# 02-CPU.net
KiCad netlist of a schematic drawn in Altium Designer
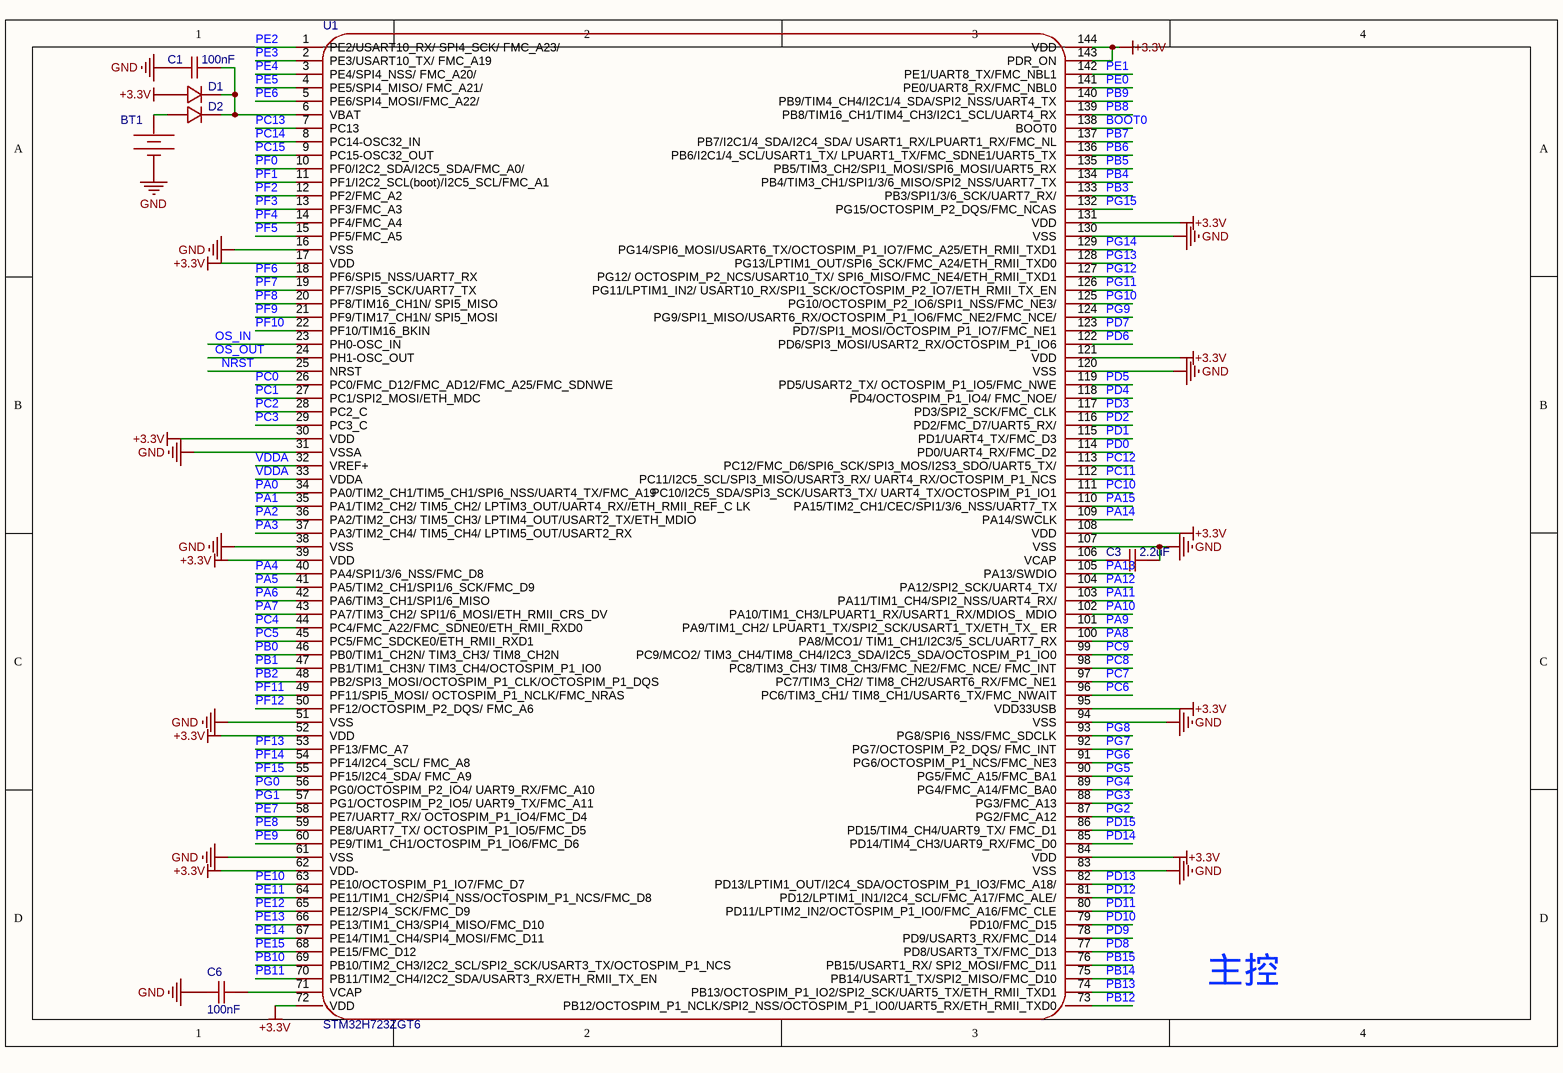
[diagram p0: 02-CPU.SchDoc]

(export (version "E")
  (design (tool "Eeschema 10.0.6"))
  (components
    (comp (ref "BT1")
      (value "BS-12-B3AA003")
      (footprint "BAT-SMD_BS-12-B3AA011")
      (description "连接器类型:电池底座;适用电池规格:CR1220;工作温度范围:-25℃~+85℃;")
      (fields (field (name "MANUFACTURER") "MYOUNG(美阳)"))
      (libsource (lib "altium-import") (part "root_3_BS-12-B3AA003_"))
    )
    (comp (ref "C1")
      (value "100nF")
      (footprint "C0603")
      (fields (field (name "Comment") "CAP_0603"))
      (libsource (lib "altium-import") (part "root_2_CAP_0603_"))
    )
    (comp (ref "C3")
      (value "2.2uF")
      (footprint "C0603")
      (fields (field (name "Comment") "CAP_0603"))
      (libsource (lib "altium-import") (part "root_2_CAP_0603_"))
    )
    (comp (ref "C6")
      (value "100nF")
      (footprint "C0603")
      (fields (field (name "Comment") "CAP_0603"))
      (libsource (lib "altium-import") (part "root_0_CAP_0603_"))
    )
    (comp (ref "D1")
      (value "LL4148_C9808")
      (footprint "LL-34_L3.5-W1.5-RD")
      (fields (field (name "MANUFACTURER") "ST(先科)") (field (name "MANUFACTURERPART") "LL4148"))
      (libsource (lib "altium-import") (part "root_2_LL4148_C9808_"))
    )
    (comp (ref "D2")
      (value "LL4148_C9808")
      (footprint "LL-34_L3.5-W1.5-RD")
      (fields (field (name "MANUFACTURER") "ST(先科)") (field (name "MANUFACTURERPART") "LL4148"))
      (libsource (lib "altium-import") (part "root_2_LL4148_C9808_"))
    )
    (comp (ref "U1")
      (value "STM32H723ZGT6")
      (footprint "LQFP-144_20.0X20.0X0.5P")
      (description "ARM-M系列 CPU最大主频：550MHz 程序存储容量：1MB 程序存储器类型：FLASH RAM总容量：564KB GPIO端口数量：80")
      (libsource (lib "altium-import") (part "root_0_STM32H723ZGT6_"))
    )
  )
  (nets
    (net (code "1") (name "+3.3V") (class "Default")
      (node (ref "D1") (pin "2") (pinfunction "A_2") (pintype "passive"))
      (node (ref "U1") (pin "108") (pinfunction "VDD_108") (pintype "passive"))
      (node (ref "U1") (pin "121") (pinfunction "VDD_121") (pintype "passive"))
      (node (ref "U1") (pin "131") (pinfunction "VDD_131") (pintype "passive"))
      (node (ref "U1") (pin "143") (pinfunction "PDR_ON_143") (pintype "passive"))
      (node (ref "U1") (pin "144") (pinfunction "VDD_144") (pintype "passive"))
      (node (ref "U1") (pin "17") (pinfunction "VDD_17") (pintype "passive"))
      (node (ref "U1") (pin "30") (pinfunction "VDD_30") (pintype "passive"))
      (node (ref "U1") (pin "39") (pinfunction "VDD_39") (pintype "passive"))
      (node (ref "U1") (pin "52") (pinfunction "VDD_52") (pintype "passive"))
      (node (ref "U1") (pin "62") (pinfunction "VDD-_62") (pintype "passive"))
      (node (ref "U1") (pin "72") (pinfunction "VDD_72") (pintype "passive"))
      (node (ref "U1") (pin "84") (pinfunction "VDD_84") (pintype "passive"))
      (node (ref "U1") (pin "95") (pinfunction "VDD33USB_95") (pintype "passive"))
    )
    (net (code "2") (name "/BOOT0") (class "Default")
      (node (ref "U1") (pin "138") (pinfunction "BOOT0_138") (pintype "passive"))
    )
    (net (code "3") (name "/NRST") (class "Default")
      (node (ref "U1") (pin "25") (pinfunction "NRST_25") (pintype "passive"))
    )
    (net (code "4") (name "/OS_IN") (class "Default")
      (node (ref "U1") (pin "23") (pinfunction "PH0-OSC_IN_23") (pintype "passive"))
    )
    (net (code "5") (name "/OS_OUT") (class "Default")
      (node (ref "U1") (pin "24") (pinfunction "PH1-OSC_OUT_24") (pintype "passive"))
    )
    (net (code "6") (name "/PA0") (class "Default")
      (node (ref "U1") (pin "34") (pinfunction "PA0/TIM2_CH1/TIM5_CH1/SPI6_NSS/UART4_TX/FMC_A19_34") (pintype "passive"))
    )
    (net (code "7") (name "/PA1") (class "Default")
      (node (ref "U1") (pin "35") (pinfunction "PA1/TIM2_CH2/_TIM5_CH2/_LPTIM3_OUT/UART4_RX//ETH_RMII_REF_C_LK_35") (pintype "passive"))
    )
    (net (code "8") (name "/PA2") (class "Default")
      (node (ref "U1") (pin "36") (pinfunction "PA2/TIM2_CH3/_TIM5_CH3/_LPTIM4_OUT/USART2_TX/ETH_MDIO_36") (pintype "passive"))
    )
    (net (code "9") (name "/PA3") (class "Default")
      (node (ref "U1") (pin "37") (pinfunction "PA3/TIM2_CH4/_TIM5_CH4/_LPTIM5_OUT/USART2_RX_37") (pintype "passive"))
    )
    (net (code "10") (name "/PA4") (class "Default")
      (node (ref "U1") (pin "40") (pinfunction "PA4/SPI1/3/6_NSS/FMC_D8_40") (pintype "passive"))
    )
    (net (code "11") (name "/PA5") (class "Default")
      (node (ref "U1") (pin "41") (pinfunction "PA5/TIM2_CH1/SPI1/6_SCK/FMC_D9_41") (pintype "passive"))
    )
    (net (code "12") (name "/PA6") (class "Default")
      (node (ref "U1") (pin "42") (pinfunction "PA6/TIM3_CH1/SPI1/6_MISO_42") (pintype "passive"))
    )
    (net (code "13") (name "/PA7") (class "Default")
      (node (ref "U1") (pin "43") (pinfunction "PA7/TIM3_CH2/_SPI1/6_MOSI/ETH_RMII_CRS_DV_43") (pintype "passive"))
    )
    (net (code "14") (name "/PA8") (class "Default")
      (node (ref "U1") (pin "100") (pinfunction "PA8/MCO1/_TIM1_CH1/I2C3/5_SCL/UART7_RX_100") (pintype "passive"))
    )
    (net (code "15") (name "/PA9") (class "Default")
      (node (ref "U1") (pin "101") (pinfunction "PA9/TIM1_CH2/_LPUART1_TX/SPI2_SCK/USART1_TX/ETH_TX__ER_101") (pintype "passive"))
    )
    (net (code "16") (name "/PA10") (class "Default")
      (node (ref "U1") (pin "102") (pinfunction "PA10/TIM1_CH3/LPUART1_RX/USART1_RX/MDIOS__MDIO_102") (pintype "passive"))
    )
    (net (code "17") (name "/PA11") (class "Default")
      (node (ref "U1") (pin "103") (pinfunction "PA11/TIM1_CH4/SPI2_NSS/UART4_RX/_103") (pintype "passive"))
    )
    (net (code "18") (name "/PA12") (class "Default")
      (node (ref "U1") (pin "104") (pinfunction "PA12/SPI2_SCK/UART4_TX/_104") (pintype "passive"))
    )
    (net (code "19") (name "/PA13") (class "Default")
      (node (ref "U1") (pin "105") (pinfunction "PA13/SWDIO_105") (pintype "passive"))
    )
    (net (code "20") (name "/PA14") (class "Default")
      (node (ref "U1") (pin "109") (pinfunction "PA14/SWCLK_109") (pintype "passive"))
    )
    (net (code "21") (name "/PA15") (class "Default")
      (node (ref "U1") (pin "110") (pinfunction "PA15/TIM2_CH1/CEC/SPI1/3/6_NSS/UART7_TX_110") (pintype "passive"))
    )
    (net (code "22") (name "/PB0") (class "Default")
      (node (ref "U1") (pin "46") (pinfunction "PB0/TIM1_CH2N/_TIM3_CH3/_TIM8_CH2N_46") (pintype "passive"))
    )
    (net (code "23") (name "/PB1") (class "Default")
      (node (ref "U1") (pin "47") (pinfunction "PB1/TIM1_CH3N/_TIM3_CH4/OCTOSPIM_P1_IO0_47") (pintype "passive"))
    )
    (net (code "24") (name "/PB2") (class "Default")
      (node (ref "U1") (pin "48") (pinfunction "PB2/SPI3_MOSI/OCTOSPIM_P1_CLK/OCTOSPIM_P1_DQS_48") (pintype "passive"))
    )
    (net (code "25") (name "/PB3") (class "Default")
      (node (ref "U1") (pin "133") (pinfunction "PB3/SPI1/3/6_SCK/UART7_RX/_133") (pintype "passive"))
    )
    (net (code "26") (name "/PB4") (class "Default")
      (node (ref "U1") (pin "134") (pinfunction "PB4/TIM3_CH1/SPI1/3/6_MISO/SPI2_NSS/UART7_TX_134") (pintype "passive"))
    )
    (net (code "27") (name "/PB5") (class "Default")
      (node (ref "U1") (pin "135") (pinfunction "PB5/TIM3_CH2/SPI1_MOSI/SPI6_MOSI/UART5_RX_135") (pintype "passive"))
    )
    (net (code "28") (name "/PB6") (class "Default")
      (node (ref "U1") (pin "136") (pinfunction "PB6/I2C1/4_SCL/USART1_TX/_LPUART1_TX/FMC_SDNE1/UART5_TX_136") (pintype "passive"))
    )
    (net (code "29") (name "/PB7") (class "Default")
      (node (ref "U1") (pin "137") (pinfunction "PB7/I2C1/4_SDA/I2C4_SDA/_USART1_RX/LPUART1_RX/FMC_NL_137") (pintype "passive"))
    )
    (net (code "30") (name "/PB8") (class "Default")
      (node (ref "U1") (pin "139") (pinfunction "PB8/TIM16_CH1/TIM4_CH3/I2C1_SCL/UART4_RX_139") (pintype "passive"))
    )
    (net (code "31") (name "/PB9") (class "Default")
      (node (ref "U1") (pin "140") (pinfunction "PB9/TIM4_CH4/I2C1/4_SDA/SPI2_NSS/UART4_TX_140") (pintype "passive"))
    )
    (net (code "32") (name "/PB10") (class "Default")
      (node (ref "U1") (pin "69") (pinfunction "PB10/TIM2_CH3/I2C2_SCL/SPI2_SCK/USART3_TX/OCTOSPIM_P1_NCS_69") (pintype "passive"))
    )
    (net (code "33") (name "/PB11") (class "Default")
      (node (ref "U1") (pin "70") (pinfunction "PB11/TIM2_CH4/I2C2_SDA/USART3_RX/ETH_RMII_TX_EN_70") (pintype "passive"))
    )
    (net (code "34") (name "/PB12") (class "Default")
      (node (ref "U1") (pin "73") (pinfunction "PB12/OCTOSPIM_P1_NCLK/SPI2_NSS/OCTOSPIM_P1_IO0/UART5_RX/ETH_RMII_TXD0_73") (pintype "passive"))
    )
    (net (code "35") (name "/PB13") (class "Default")
      (node (ref "U1") (pin "74") (pinfunction "PB13/OCTOSPIM_P1_IO2/SPI2_SCK/UART5_TX/ETH_RMII_TXD1_74") (pintype "passive"))
    )
    (net (code "36") (name "/PB14") (class "Default")
      (node (ref "U1") (pin "75") (pinfunction "PB14/USART1_TX/SPI2_MISO/FMC_D10_75") (pintype "passive"))
    )
    (net (code "37") (name "/PB15") (class "Default")
      (node (ref "U1") (pin "76") (pinfunction "PB15/USART1_RX/_SPI2_MOSI/FMC_D11_76") (pintype "passive"))
    )
    (net (code "38") (name "/PC0") (class "Default")
      (node (ref "U1") (pin "26") (pinfunction "PC0/FMC_D12/FMC_AD12/FMC_A25/FMC_SDNWE_26") (pintype "passive"))
    )
    (net (code "39") (name "/PC1") (class "Default")
      (node (ref "U1") (pin "27") (pinfunction "PC1/SPI2_MOSI/ETH_MDC_27") (pintype "passive"))
    )
    (net (code "40") (name "/PC2") (class "Default")
      (node (ref "U1") (pin "28") (pinfunction "PC2_C_28") (pintype "passive"))
    )
    (net (code "41") (name "/PC3") (class "Default")
      (node (ref "U1") (pin "29") (pinfunction "PC3_C_29") (pintype "passive"))
    )
    (net (code "42") (name "/PC4") (class "Default")
      (node (ref "U1") (pin "44") (pinfunction "PC4/FMC_A22/FMC_SDNE0/ETH_RMII_RXD0_44") (pintype "passive"))
    )
    (net (code "43") (name "/PC5") (class "Default")
      (node (ref "U1") (pin "45") (pinfunction "PC5/FMC_SDCKE0/ETH_RMII_RXD1_45") (pintype "passive"))
    )
    (net (code "44") (name "/PC6") (class "Default")
      (node (ref "U1") (pin "96") (pinfunction "PC6/TIM3_CH1/_TIM8_CH1/USART6_TX/FMC_NWAIT_96") (pintype "passive"))
    )
    (net (code "45") (name "/PC7") (class "Default")
      (node (ref "U1") (pin "97") (pinfunction "PC7/TIM3_CH2/_TIM8_CH2/USART6_RX/FMC_NE1_97") (pintype "passive"))
    )
    (net (code "46") (name "/PC8") (class "Default")
      (node (ref "U1") (pin "98") (pinfunction "PC8/TIM3_CH3/_TIM8_CH3/FMC_NE2/FMC_NCE/_FMC_INT_98") (pintype "passive"))
    )
    (net (code "47") (name "/PC9") (class "Default")
      (node (ref "U1") (pin "99") (pinfunction "PC9/MCO2/_TIM3_CH4/TIM8_CH4/I2C3_SDA/I2C5_SDA/OCTOSPIM_P1_IO0_99") (pintype "passive"))
    )
    (net (code "48") (name "/PC10") (class "Default")
      (node (ref "U1") (pin "111") (pinfunction "PC10/I2C5_SDA/SPI3_SCK/USART3_TX/_UART4_TX/OCTOSPIM_P1_IO1_111") (pintype "passive"))
    )
    (net (code "49") (name "/PC11") (class "Default")
      (node (ref "U1") (pin "112") (pinfunction "PC11/I2C5_SCL/SPI3_MISO/USART3_RX/_UART4_RX/OCTOSPIM_P1_NCS_112") (pintype "passive"))
    )
    (net (code "50") (name "/PC12") (class "Default")
      (node (ref "U1") (pin "113") (pinfunction "PC12/FMC_D6/SPI6_SCK/SPI3_MOS/I2S3_SDO/UART5_TX/_113") (pintype "passive"))
    )
    (net (code "51") (name "/PC13") (class "Default")
      (node (ref "U1") (pin "7") (pinfunction "PC13_7") (pintype "passive"))
    )
    (net (code "52") (name "/PC14") (class "Default")
      (node (ref "U1") (pin "8") (pinfunction "PC14-OSC32_IN_8") (pintype "passive"))
    )
    (net (code "53") (name "/PC15") (class "Default")
      (node (ref "U1") (pin "9") (pinfunction "PC15-OSC32_OUT_9") (pintype "passive"))
    )
    (net (code "54") (name "/PD0") (class "Default")
      (node (ref "U1") (pin "114") (pinfunction "PD0/UART4_RX/FMC_D2_114") (pintype "passive"))
    )
    (net (code "55") (name "/PD1") (class "Default")
      (node (ref "U1") (pin "115") (pinfunction "PD1/UART4_TX/FMC_D3_115") (pintype "passive"))
    )
    (net (code "56") (name "/PD2") (class "Default")
      (node (ref "U1") (pin "116") (pinfunction "PD2/FMC_D7/UART5_RX/_116") (pintype "passive"))
    )
    (net (code "57") (name "/PD3") (class "Default")
      (node (ref "U1") (pin "117") (pinfunction "PD3/SPI2_SCK/FMC_CLK_117") (pintype "passive"))
    )
    (net (code "58") (name "/PD4") (class "Default")
      (node (ref "U1") (pin "118") (pinfunction "PD4/OCTOSPIM_P1_IO4/_FMC_NOE/_118") (pintype "passive"))
    )
    (net (code "59") (name "/PD5") (class "Default")
      (node (ref "U1") (pin "119") (pinfunction "PD5/USART2_TX/_OCTOSPIM_P1_IO5/FMC_NWE_119") (pintype "passive"))
    )
    (net (code "60") (name "/PD6") (class "Default")
      (node (ref "U1") (pin "122") (pinfunction "PD6/SPI3_MOSI/USART2_RX/OCTOSPIM_P1_IO6_122") (pintype "passive"))
    )
    (net (code "61") (name "/PD7") (class "Default")
      (node (ref "U1") (pin "123") (pinfunction "PD7/SPI1_MOSI/OCTOSPIM_P1_IO7/FMC_NE1_123") (pintype "passive"))
    )
    (net (code "62") (name "/PD8") (class "Default")
      (node (ref "U1") (pin "77") (pinfunction "PD8/USART3_TX/FMC_D13_77") (pintype "passive"))
    )
    (net (code "63") (name "/PD9") (class "Default")
      (node (ref "U1") (pin "78") (pinfunction "PD9/USART3_RX/FMC_D14_78") (pintype "passive"))
    )
    (net (code "64") (name "/PD10") (class "Default")
      (node (ref "U1") (pin "79") (pinfunction "PD10/FMC_D15_79") (pintype "passive"))
    )
    (net (code "65") (name "/PD11") (class "Default")
      (node (ref "U1") (pin "80") (pinfunction "PD11/LPTIM2_IN2/OCTOSPIM_P1_IO0/FMC_A16/FMC_CLE_80") (pintype "passive"))
    )
    (net (code "66") (name "/PD12") (class "Default")
      (node (ref "U1") (pin "81") (pinfunction "PD12/LPTIM1_IN1/I2C4_SCL/FMC_A17/FMC_ALE/_81") (pintype "passive"))
    )
    (net (code "67") (name "/PD13") (class "Default")
      (node (ref "U1") (pin "82") (pinfunction "PD13/LPTIM1_OUT/I2C4_SDA/OCTOSPIM_P1_IO3/FMC_A18/_82") (pintype "passive"))
    )
    (net (code "68") (name "/PD14") (class "Default")
      (node (ref "U1") (pin "85") (pinfunction "PD14/TIM4_CH3/UART9_RX/FMC_D0_85") (pintype "passive"))
    )
    (net (code "69") (name "/PD15") (class "Default")
      (node (ref "U1") (pin "86") (pinfunction "PD15/TIM4_CH4/UART9_TX/_FMC_D1_86") (pintype "passive"))
    )
    (net (code "70") (name "/PE0") (class "Default")
      (node (ref "U1") (pin "141") (pinfunction "PE0/UART8_RX/FMC_NBL0_141") (pintype "passive"))
    )
    (net (code "71") (name "/PE1") (class "Default")
      (node (ref "U1") (pin "142") (pinfunction "PE1/UART8_TX/FMC_NBL1_142") (pintype "passive"))
    )
    (net (code "72") (name "/PE2") (class "Default")
      (node (ref "U1") (pin "1") (pinfunction "PE2/USART10_RX/_SPI4_SCK/_FMC_A23/_1") (pintype "passive"))
    )
    (net (code "73") (name "/PE3") (class "Default")
      (node (ref "U1") (pin "2") (pinfunction "PE3/USART10_TX/_FMC_A19_2") (pintype "passive"))
    )
    (net (code "74") (name "/PE4") (class "Default")
      (node (ref "U1") (pin "3") (pinfunction "PE4/SPI4_NSS/_FMC_A20/_3") (pintype "passive"))
    )
    (net (code "75") (name "/PE5") (class "Default")
      (node (ref "U1") (pin "4") (pinfunction "PE5/SPI4_MISO/_FMC_A21/_4") (pintype "passive"))
    )
    (net (code "76") (name "/PE6") (class "Default")
      (node (ref "U1") (pin "5") (pinfunction "PE6/SPI4_MOSI/FMC_A22/_5") (pintype "passive"))
    )
    (net (code "77") (name "/PE7") (class "Default")
      (node (ref "U1") (pin "58") (pinfunction "PE7/UART7_RX/_OCTOSPIM_P1_IO4/FMC_D4_58") (pintype "passive"))
    )
    (net (code "78") (name "/PE8") (class "Default")
      (node (ref "U1") (pin "59") (pinfunction "PE8/UART7_TX/_OCTOSPIM_P1_IO5/FMC_D5_59") (pintype "passive"))
    )
    (net (code "79") (name "/PE9") (class "Default")
      (node (ref "U1") (pin "60") (pinfunction "PE9/TIM1_CH1/OCTOSPIM_P1_IO6/FMC_D6_60") (pintype "passive"))
    )
    (net (code "80") (name "/PE10") (class "Default")
      (node (ref "U1") (pin "63") (pinfunction "PE10/OCTOSPIM_P1_IO7/FMC_D7_63") (pintype "passive"))
    )
    (net (code "81") (name "/PE11") (class "Default")
      (node (ref "U1") (pin "64") (pinfunction "PE11/TIM1_CH2/SPI4_NSS/OCTOSPIM_P1_NCS/FMC_D8_64") (pintype "passive"))
    )
    (net (code "82") (name "/PE12") (class "Default")
      (node (ref "U1") (pin "65") (pinfunction "PE12/SPI4_SCK/FMC_D9_65") (pintype "passive"))
    )
    (net (code "83") (name "/PE13") (class "Default")
      (node (ref "U1") (pin "66") (pinfunction "PE13/TIM1_CH3/SPI4_MISO/FMC_D10_66") (pintype "passive"))
    )
    (net (code "84") (name "/PE14") (class "Default")
      (node (ref "U1") (pin "67") (pinfunction "PE14/TIM1_CH4/SPI4_MOSI/FMC_D11_67") (pintype "passive"))
    )
    (net (code "85") (name "/PE15") (class "Default")
      (node (ref "U1") (pin "68") (pinfunction "PE15/FMC_D12_68") (pintype "passive"))
    )
    (net (code "86") (name "/PF0") (class "Default")
      (node (ref "U1") (pin "10") (pinfunction "PF0/I2C2_SDA/I2C5_SDA/FMC_A0/_10") (pintype "passive"))
    )
    (net (code "87") (name "/PF1") (class "Default")
      (node (ref "U1") (pin "11") (pinfunction "PF1/I2C2_SCL(boot)/I2C5_SCL/FMC_A1_11") (pintype "passive"))
    )
    (net (code "88") (name "/PF2") (class "Default")
      (node (ref "U1") (pin "12") (pinfunction "PF2/FMC_A2_12") (pintype "passive"))
    )
    (net (code "89") (name "/PF3") (class "Default")
      (node (ref "U1") (pin "13") (pinfunction "PF3/FMC_A3_13") (pintype "passive"))
    )
    (net (code "90") (name "/PF4") (class "Default")
      (node (ref "U1") (pin "14") (pinfunction "PF4/FMC_A4_14") (pintype "passive"))
    )
    (net (code "91") (name "/PF5") (class "Default")
      (node (ref "U1") (pin "15") (pinfunction "PF5/FMC_A5_15") (pintype "passive"))
    )
    (net (code "92") (name "/PF6") (class "Default")
      (node (ref "U1") (pin "18") (pinfunction "PF6/SPI5_NSS/UART7_RX_18") (pintype "passive"))
    )
    (net (code "93") (name "/PF7") (class "Default")
      (node (ref "U1") (pin "19") (pinfunction "PF7/SPI5_SCK/UART7_TX_19") (pintype "passive"))
    )
    (net (code "94") (name "/PF8") (class "Default")
      (node (ref "U1") (pin "20") (pinfunction "PF8/TIM16_CH1N/_SPI5_MISO_20") (pintype "passive"))
    )
    (net (code "95") (name "/PF9") (class "Default")
      (node (ref "U1") (pin "21") (pinfunction "PF9/TIM17_CH1N/_SPI5_MOSI_21") (pintype "passive"))
    )
    (net (code "96") (name "/PF10") (class "Default")
      (node (ref "U1") (pin "22") (pinfunction "PF10/TIM16_BKIN_22") (pintype "passive"))
    )
    (net (code "97") (name "/PF11") (class "Default")
      (node (ref "U1") (pin "49") (pinfunction "PF11/SPI5_MOSI/_OCTOSPIM_P1_NCLK/FMC_NRAS_49") (pintype "passive"))
    )
    (net (code "98") (name "/PF12") (class "Default")
      (node (ref "U1") (pin "50") (pinfunction "PF12/OCTOSPIM_P2_DQS/_FMC_A6_50") (pintype "passive"))
    )
    (net (code "99") (name "/PF13") (class "Default")
      (node (ref "U1") (pin "53") (pinfunction "PF13/FMC_A7_53") (pintype "passive"))
    )
    (net (code "100") (name "/PF14") (class "Default")
      (node (ref "U1") (pin "54") (pinfunction "PF14/I2C4_SCL/_FMC_A8_54") (pintype "passive"))
    )
    (net (code "101") (name "/PF15") (class "Default")
      (node (ref "U1") (pin "55") (pinfunction "PF15/I2C4_SDA/_FMC_A9_55") (pintype "passive"))
    )
    (net (code "102") (name "/PG0") (class "Default")
      (node (ref "U1") (pin "56") (pinfunction "PG0/OCTOSPIM_P2_IO4/_UART9_RX/FMC_A10_56") (pintype "passive"))
    )
    (net (code "103") (name "/PG1") (class "Default")
      (node (ref "U1") (pin "57") (pinfunction "PG1/OCTOSPIM_P2_IO5/_UART9_TX/FMC_A11_57") (pintype "passive"))
    )
    (net (code "104") (name "/PG2") (class "Default")
      (node (ref "U1") (pin "87") (pinfunction "PG2/FMC_A12_87") (pintype "passive"))
    )
    (net (code "105") (name "/PG3") (class "Default")
      (node (ref "U1") (pin "88") (pinfunction "PG3/FMC_A13_88") (pintype "passive"))
    )
    (net (code "106") (name "/PG4") (class "Default")
      (node (ref "U1") (pin "89") (pinfunction "PG4/FMC_A14/FMC_BA0_89") (pintype "passive"))
    )
    (net (code "107") (name "/PG5") (class "Default")
      (node (ref "U1") (pin "90") (pinfunction "PG5/FMC_A15/FMC_BA1_90") (pintype "passive"))
    )
    (net (code "108") (name "/PG6") (class "Default")
      (node (ref "U1") (pin "91") (pinfunction "PG6/OCTOSPIM_P1_NCS/FMC_NE3_91") (pintype "passive"))
    )
    (net (code "109") (name "/PG7") (class "Default")
      (node (ref "U1") (pin "92") (pinfunction "PG7/OCTOSPIM_P2_DQS/_FMC_INT_92") (pintype "passive"))
    )
    (net (code "110") (name "/PG8") (class "Default")
      (node (ref "U1") (pin "93") (pinfunction "PG8/SPI6_NSS/FMC_SDCLK_93") (pintype "passive"))
    )
    (net (code "111") (name "/PG9") (class "Default")
      (node (ref "U1") (pin "124") (pinfunction "PG9/SPI1_MISO/USART6_RX/OCTOSPIM_P1_IO6/FMC_NE2/FMC_NCE/_124") (pintype "passive"))
    )
    (net (code "112") (name "/PG10") (class "Default")
      (node (ref "U1") (pin "125") (pinfunction "PG10/OCTOSPIM_P2_IO6/SPI1_NSS/FMC_NE3/_125") (pintype "passive"))
    )
    (net (code "113") (name "/PG11") (class "Default")
      (node (ref "U1") (pin "126") (pinfunction "PG11/LPTIM1_IN2/_USART10_RX/SPI1_SCK/OCTOSPIM_P2_IO7/ETH_RMII_TX_EN_126") (pintype "passive"))
    )
    (net (code "114") (name "/PG12") (class "Default")
      (node (ref "U1") (pin "127") (pinfunction "PG12/_OCTOSPIM_P2_NCS/USART10_TX/_SPI6_MISO/FMC_NE4/ETH_RMII_TXD1_127") (pintype "passive"))
    )
    (net (code "115") (name "/PG13") (class "Default")
      (node (ref "U1") (pin "128") (pinfunction "PG13/LPTIM1_OUT/SPI6_SCK/FMC_A24/ETH_RMII_TXD0_128") (pintype "passive"))
    )
    (net (code "116") (name "/PG14") (class "Default")
      (node (ref "U1") (pin "129") (pinfunction "PG14/SPI6_MOSI/USART6_TX/OCTOSPIM_P1_IO7/FMC_A25/ETH_RMII_TXD1_129") (pintype "passive"))
    )
    (net (code "117") (name "/PG15") (class "Default")
      (node (ref "U1") (pin "132") (pinfunction "PG15/OCTOSPIM_P2_DQS/FMC_NCAS_132") (pintype "passive"))
    )
    (net (code "118") (name "/VDDA") (class "Default")
      (node (ref "U1") (pin "32") (pinfunction "VREF+_32") (pintype "passive"))
      (node (ref "U1") (pin "33") (pinfunction "VDDA_33") (pintype "passive"))
    )
    (net (code "119") (name "GND") (class "Default")
      (node (ref "BT1") (pin "2") (pinfunction "-_2") (pintype "passive"))
      (node (ref "C1") (pin "2") (pinfunction "2_2") (pintype "passive"))
      (node (ref "C3") (pin "1") (pinfunction "1_1") (pintype "passive"))
      (node (ref "C6") (pin "1") (pinfunction "1_1") (pintype "passive"))
      (node (ref "U1") (pin "107") (pinfunction "VSS_107") (pintype "passive"))
      (node (ref "U1") (pin "120") (pinfunction "VSS_120") (pintype "passive"))
      (node (ref "U1") (pin "130") (pinfunction "VSS_130") (pintype "passive"))
      (node (ref "U1") (pin "16") (pinfunction "VSS_16") (pintype "passive"))
      (node (ref "U1") (pin "31") (pinfunction "VSSA_31") (pintype "passive"))
      (node (ref "U1") (pin "38") (pinfunction "VSS_38") (pintype "passive"))
      (node (ref "U1") (pin "51") (pinfunction "VSS_51") (pintype "passive"))
      (node (ref "U1") (pin "61") (pinfunction "VSS_61") (pintype "passive"))
      (node (ref "U1") (pin "83") (pinfunction "VSS_83") (pintype "passive"))
      (node (ref "U1") (pin "94") (pinfunction "VSS_94") (pintype "passive"))
    )
    (net (code "120") (name "Net-(BT1-+)") (class "Default")
      (node (ref "BT1") (pin "1") (pinfunction "+_1") (pintype "passive"))
      (node (ref "D2") (pin "2") (pinfunction "A_2") (pintype "passive"))
    )
    (net (code "121") (name "Net-(C3-Pad2)") (class "Default")
      (node (ref "C3") (pin "2") (pinfunction "2_2") (pintype "passive"))
      (node (ref "U1") (pin "106") (pinfunction "VCAP_106") (pintype "passive"))
    )
    (net (code "122") (name "Net-(C6-Pad2)") (class "Default")
      (node (ref "C6") (pin "2") (pinfunction "2_2") (pintype "passive"))
      (node (ref "U1") (pin "71") (pinfunction "VCAP_71") (pintype "passive"))
    )
    (net (code "123") (name "Net-(D1-K)") (class "Default")
      (node (ref "C1") (pin "1") (pinfunction "1_1") (pintype "passive"))
      (node (ref "D1") (pin "1") (pinfunction "K_1") (pintype "passive"))
      (node (ref "D2") (pin "1") (pinfunction "K_1") (pintype "passive"))
      (node (ref "U1") (pin "6") (pinfunction "VBAT_6") (pintype "passive"))
    )
  )
)
